# KlokWave_Display.net
KiCad netlist of a schematic drawn in Altium Designer
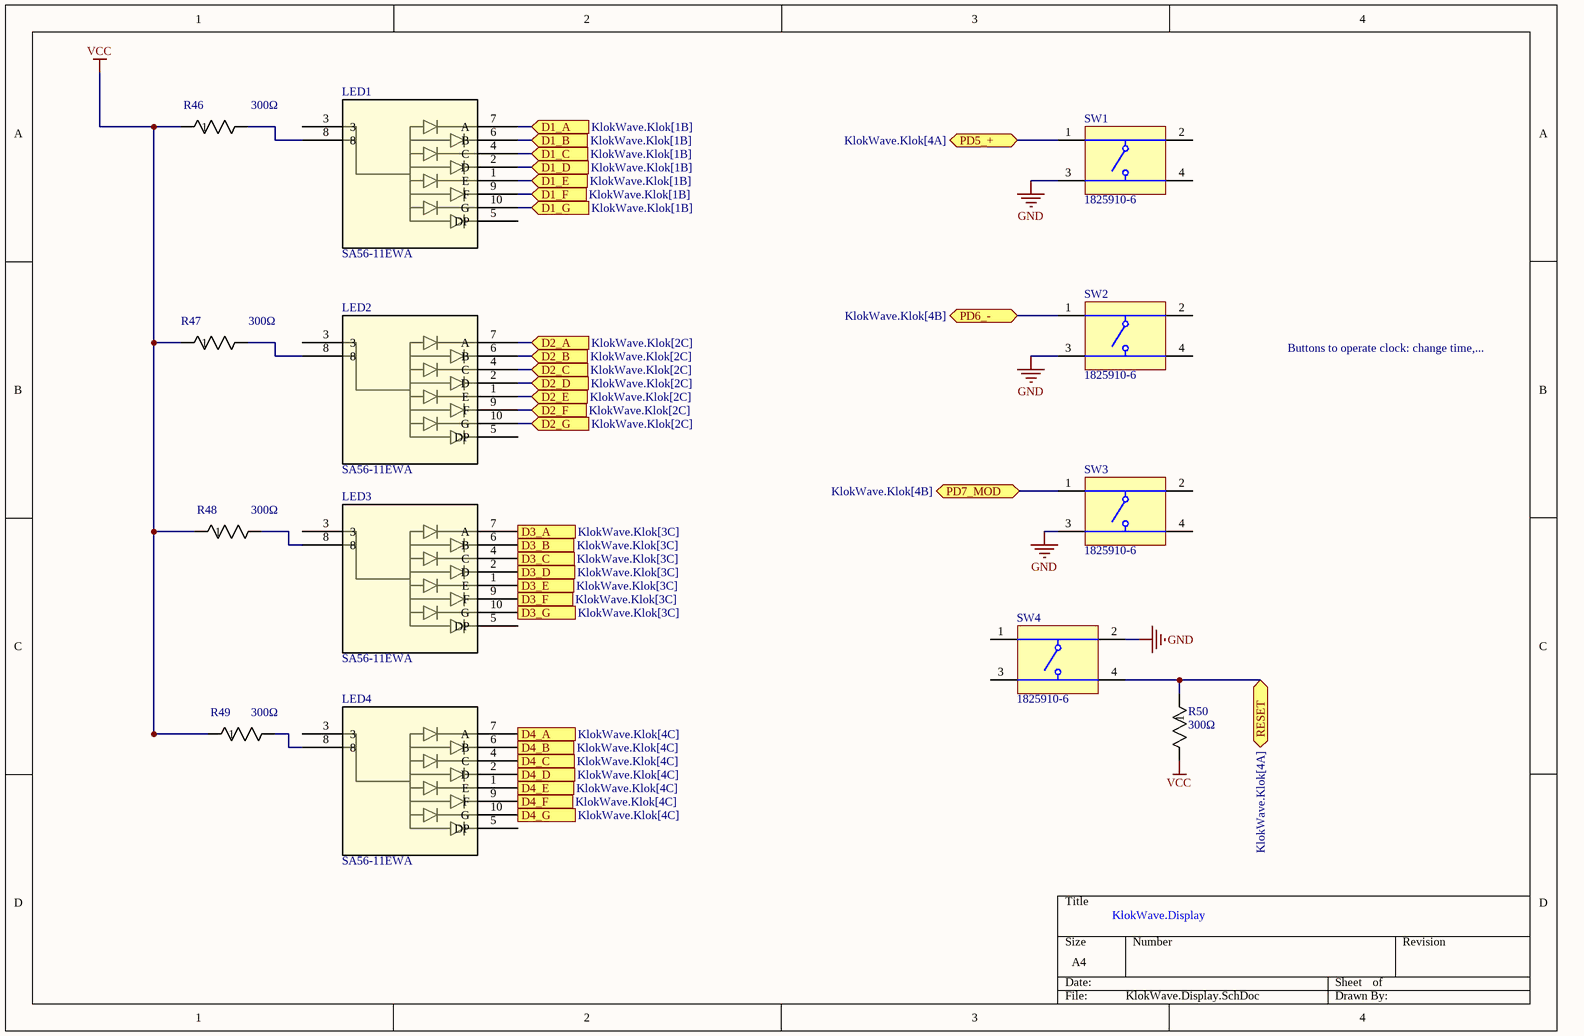
[diagram p0: KlokWave.Display.SchDoc]

(export (version "E")
  (design (tool "Eeschema 10.0.6"))
  (components
    (comp (ref "LED1")
      (value "SA56-11EWA")
      (footprint "THT 7Seg: LED10_SA56-11EWA_KNB")
      (description "THT CA 7SegDisplay")
      (libsource (lib "KlokWave") (part "SA56-11EWA"))
    )
    (comp (ref "LED2")
      (value "SA56-11EWA")
      (footprint "THT 7Seg: LED10_SA56-11EWA_KNB")
      (description "THT CA 7SegDisplay")
      (libsource (lib "KlokWave") (part "SA56-11EWA"))
    )
    (comp (ref "LED3")
      (value "SA56-11EWA")
      (footprint "THT 7Seg: LED10_SA56-11EWA_KNB")
      (description "THT CA 7SegDisplay")
      (libsource (lib "KlokWave") (part "SA56-11EWA"))
    )
    (comp (ref "LED4")
      (value "SA56-11EWA")
      (footprint "THT 7Seg: LED10_SA56-11EWA_KNB")
      (description "THT CA 7SegDisplay")
      (libsource (lib "KlokWave") (part "SA56-11EWA"))
    )
    (comp (ref "R46")
      (value "AC03000003000JAC00")
      (footprint "THT Resistor: RES_AC03_VIS")
      (description "AC03000003000JAC00 Res Wirewound THT")
      (fields (field (name "TOLERANCE") "5%") (field (name "RESISTANCE") "300Ω"))
      (libsource (lib "KlokWave") (part "CMP-00030-39746760-1"))
    )
    (comp (ref "R47")
      (value "AC03000003000JAC00")
      (footprint "THT Resistor: RES_AC03_VIS")
      (description "AC03000003000JAC00 Res Wirewound THT")
      (fields (field (name "TOLERANCE") "5%") (field (name "RESISTANCE") "300Ω"))
      (libsource (lib "KlokWave") (part "CMP-00030-39746760-1"))
    )
    (comp (ref "R48")
      (value "AC03000003000JAC00")
      (footprint "THT Resistor: RES_AC03_VIS")
      (description "AC03000003000JAC00 Res Wirewound THT")
      (fields (field (name "TOLERANCE") "5%") (field (name "RESISTANCE") "300Ω"))
      (libsource (lib "KlokWave") (part "CMP-00030-39746760-1"))
    )
    (comp (ref "R49")
      (value "AC03000003000JAC00")
      (footprint "THT Resistor: RES_AC03_VIS")
      (description "AC03000003000JAC00 Res Wirewound THT")
      (fields (field (name "TOLERANCE") "5%") (field (name "RESISTANCE") "300Ω"))
      (libsource (lib "KlokWave") (part "CMP-00030-39746760-1"))
    )
    (comp (ref "R50")
      (value "AC03000003000JAC00")
      (footprint "THT Resistor: RES_AC03_VIS")
      (description "AC03000003000JAC00 Res Wirewound THT")
      (fields (field (name "TOLERANCE") "5%") (field (name "RESISTANCE") "300Ω"))
      (libsource (lib "KlokWave") (part "CMP-00030-39746760-1"))
    )
    (comp (ref "SW1")
      (value "1825910-6")
      (footprint "THT Button: TECO-1825910-6_V")
      (description "THT Tact Switch, SPST-NO, 0.05 A, -35 to 85 degC, 4-Pin THD, RoHS, Bulk")
      (fields (field (name "MANUFACTURER") "TE Connectivity"))
      (libsource (lib "KlokWave") (part "CMP-1684-00021-1"))
    )
    (comp (ref "SW2")
      (value "1825910-6")
      (footprint "THT Button: TECO-1825910-6_V")
      (description "THT Tact Switch, SPST-NO, 0.05 A, -35 to 85 degC, 4-Pin THD, RoHS, Bulk")
      (fields (field (name "MANUFACTURER") "TE Connectivity"))
      (libsource (lib "KlokWave") (part "CMP-1684-00021-1"))
    )
    (comp (ref "SW3")
      (value "1825910-6")
      (footprint "THT Button: TECO-1825910-6_V")
      (description "THT Tact Switch, SPST-NO, 0.05 A, -35 to 85 degC, 4-Pin THD, RoHS, Bulk")
      (fields (field (name "MANUFACTURER") "TE Connectivity"))
      (libsource (lib "KlokWave") (part "CMP-1684-00021-1"))
    )
    (comp (ref "SW4")
      (value "1825910-6")
      (footprint "THT Button: TECO-1825910-6_V")
      (description "THT Tact Switch, SPST-NO, 0.05 A, -35 to 85 degC, 4-Pin THD, RoHS, Bulk")
      (fields (field (name "MANUFACTURER") "TE Connectivity"))
      (libsource (lib "KlokWave") (part "CMP-1684-00021-1"))
    )
  )
  (nets
    (net (code "1") (name "/D1_A") (class "Default")
      (node (ref "LED1") (pin "7") (pinfunction "A_7") (pintype "passive"))
    )
    (net (code "2") (name "/D1_B") (class "Default")
      (node (ref "LED1") (pin "6") (pinfunction "B_6") (pintype "passive"))
    )
    (net (code "3") (name "/D1_C") (class "Default")
      (node (ref "LED1") (pin "4") (pinfunction "C_4") (pintype "passive"))
    )
    (net (code "4") (name "/D1_D") (class "Default")
      (node (ref "LED1") (pin "2") (pinfunction "D_2") (pintype "passive"))
    )
    (net (code "5") (name "/D1_E") (class "Default")
      (node (ref "LED1") (pin "1") (pinfunction "E_1") (pintype "passive"))
    )
    (net (code "6") (name "/D1_F") (class "Default")
      (node (ref "LED1") (pin "9") (pinfunction "F_9") (pintype "passive"))
    )
    (net (code "7") (name "/D1_G") (class "Default")
      (node (ref "LED1") (pin "10") (pinfunction "G_10") (pintype "passive"))
    )
    (net (code "8") (name "/D2_A") (class "Default")
      (node (ref "LED2") (pin "7") (pinfunction "A_7") (pintype "passive"))
    )
    (net (code "9") (name "/D2_B") (class "Default")
      (node (ref "LED2") (pin "6") (pinfunction "B_6") (pintype "passive"))
    )
    (net (code "10") (name "/D2_C") (class "Default")
      (node (ref "LED2") (pin "4") (pinfunction "C_4") (pintype "passive"))
    )
    (net (code "11") (name "/D2_D") (class "Default")
      (node (ref "LED2") (pin "2") (pinfunction "D_2") (pintype "passive"))
    )
    (net (code "12") (name "/D2_E") (class "Default")
      (node (ref "LED2") (pin "1") (pinfunction "E_1") (pintype "passive"))
    )
    (net (code "13") (name "/D2_F") (class "Default")
      (node (ref "LED2") (pin "9") (pinfunction "F_9") (pintype "passive"))
    )
    (net (code "14") (name "/D2_G") (class "Default")
      (node (ref "LED2") (pin "10") (pinfunction "G_10") (pintype "passive"))
    )
    (net (code "15") (name "/D3_A") (class "Default")
      (node (ref "LED3") (pin "7") (pinfunction "A_7") (pintype "passive"))
    )
    (net (code "16") (name "/D3_B") (class "Default")
      (node (ref "LED3") (pin "6") (pinfunction "B_6") (pintype "passive"))
    )
    (net (code "17") (name "/D3_C") (class "Default")
      (node (ref "LED3") (pin "4") (pinfunction "C_4") (pintype "passive"))
    )
    (net (code "18") (name "/D3_D") (class "Default")
      (node (ref "LED3") (pin "2") (pinfunction "D_2") (pintype "passive"))
    )
    (net (code "19") (name "/D3_E") (class "Default")
      (node (ref "LED3") (pin "1") (pinfunction "E_1") (pintype "passive"))
    )
    (net (code "20") (name "/D3_F") (class "Default")
      (node (ref "LED3") (pin "9") (pinfunction "F_9") (pintype "passive"))
    )
    (net (code "21") (name "/D3_G") (class "Default")
      (node (ref "LED3") (pin "10") (pinfunction "G_10") (pintype "passive"))
    )
    (net (code "22") (name "/D4_A") (class "Default")
      (node (ref "LED4") (pin "7") (pinfunction "A_7") (pintype "passive"))
    )
    (net (code "23") (name "/D4_B") (class "Default")
      (node (ref "LED4") (pin "6") (pinfunction "B_6") (pintype "passive"))
    )
    (net (code "24") (name "/D4_C") (class "Default")
      (node (ref "LED4") (pin "4") (pinfunction "C_4") (pintype "passive"))
    )
    (net (code "25") (name "/D4_D") (class "Default")
      (node (ref "LED4") (pin "2") (pinfunction "D_2") (pintype "passive"))
    )
    (net (code "26") (name "/D4_E") (class "Default")
      (node (ref "LED4") (pin "1") (pinfunction "E_1") (pintype "passive"))
    )
    (net (code "27") (name "/D4_F") (class "Default")
      (node (ref "LED4") (pin "9") (pinfunction "F_9") (pintype "passive"))
    )
    (net (code "28") (name "/D4_G") (class "Default")
      (node (ref "LED4") (pin "10") (pinfunction "G_10") (pintype "passive"))
    )
    (net (code "29") (name "/PD5_+") (class "Default")
      (node (ref "SW1") (pin "1") (pinfunction "1_1") (pintype "passive"))
    )
    (net (code "30") (name "/PD6_-") (class "Default")
      (node (ref "SW2") (pin "1") (pinfunction "1_1") (pintype "passive"))
    )
    (net (code "31") (name "/PD7_MOD") (class "Default")
      (node (ref "SW3") (pin "1") (pinfunction "1_1") (pintype "passive"))
    )
    (net (code "32") (name "/RESET") (class "Default")
      (node (ref "R50") (pin "1") (pinfunction "1_1") (pintype "passive"))
      (node (ref "SW4") (pin "4") (pinfunction "4_4") (pintype "passive"))
    )
    (net (code "33") (name "GND") (class "Default")
      (node (ref "SW1") (pin "3") (pinfunction "3_3") (pintype "passive"))
      (node (ref "SW2") (pin "3") (pinfunction "3_3") (pintype "passive"))
      (node (ref "SW3") (pin "3") (pinfunction "3_3") (pintype "passive"))
      (node (ref "SW4") (pin "2") (pinfunction "2_2") (pintype "passive"))
    )
    (net (code "34") (name "Net-(LED1-Pad8)") (class "Default")
      (node (ref "LED1") (pin "8") (pinfunction "8_8") (pintype "passive"))
      (node (ref "R46") (pin "2") (pinfunction "2_2") (pintype "passive"))
    )
    (net (code "35") (name "Net-(LED2-Pad8)") (class "Default")
      (node (ref "LED2") (pin "8") (pinfunction "8_8") (pintype "passive"))
      (node (ref "R47") (pin "2") (pinfunction "2_2") (pintype "passive"))
    )
    (net (code "36") (name "Net-(LED3-Pad8)") (class "Default")
      (node (ref "LED3") (pin "8") (pinfunction "8_8") (pintype "passive"))
      (node (ref "R48") (pin "2") (pinfunction "2_2") (pintype "passive"))
    )
    (net (code "37") (name "Net-(LED4-Pad8)") (class "Default")
      (node (ref "LED4") (pin "8") (pinfunction "8_8") (pintype "passive"))
      (node (ref "R49") (pin "2") (pinfunction "2_2") (pintype "passive"))
    )
    (net (code "38") (name "VCC") (class "Default")
      (node (ref "R46") (pin "1") (pinfunction "1_1") (pintype "passive"))
      (node (ref "R47") (pin "1") (pinfunction "1_1") (pintype "passive"))
      (node (ref "R48") (pin "1") (pinfunction "1_1") (pintype "passive"))
      (node (ref "R49") (pin "1") (pinfunction "1_1") (pintype "passive"))
      (node (ref "R50") (pin "2") (pinfunction "2_2") (pintype "passive"))
    )
    (net (code "39") (name "unconnected-(LED1-DP-Pad5)") (class "Default")
      (node (ref "LED1") (pin "5") (pinfunction "DP_5") (pintype "passive"))
    )
    (net (code "40") (name "unconnected-(LED1-Pad3)") (class "Default")
      (node (ref "LED1") (pin "3") (pinfunction "3_3") (pintype "passive"))
    )
    (net (code "41") (name "unconnected-(LED2-DP-Pad5)") (class "Default")
      (node (ref "LED2") (pin "5") (pinfunction "DP_5") (pintype "passive"))
    )
    (net (code "42") (name "unconnected-(LED2-Pad3)") (class "Default")
      (node (ref "LED2") (pin "3") (pinfunction "3_3") (pintype "passive"))
    )
    (net (code "43") (name "unconnected-(LED3-DP-Pad5)") (class "Default")
      (node (ref "LED3") (pin "5") (pinfunction "DP_5") (pintype "passive"))
    )
    (net (code "44") (name "unconnected-(LED3-Pad3)") (class "Default")
      (node (ref "LED3") (pin "3") (pinfunction "3_3") (pintype "passive"))
    )
    (net (code "45") (name "unconnected-(LED4-DP-Pad5)") (class "Default")
      (node (ref "LED4") (pin "5") (pinfunction "DP_5") (pintype "passive"))
    )
    (net (code "46") (name "unconnected-(LED4-Pad3)") (class "Default")
      (node (ref "LED4") (pin "3") (pinfunction "3_3") (pintype "passive"))
    )
    (net (code "47") (name "unconnected-(SW1-Pad2)") (class "Default")
      (node (ref "SW1") (pin "2") (pinfunction "2_2") (pintype "passive"))
    )
    (net (code "48") (name "unconnected-(SW1-Pad4)") (class "Default")
      (node (ref "SW1") (pin "4") (pinfunction "4_4") (pintype "passive"))
    )
    (net (code "49") (name "unconnected-(SW2-Pad2)") (class "Default")
      (node (ref "SW2") (pin "2") (pinfunction "2_2") (pintype "passive"))
    )
    (net (code "50") (name "unconnected-(SW2-Pad4)") (class "Default")
      (node (ref "SW2") (pin "4") (pinfunction "4_4") (pintype "passive"))
    )
    (net (code "51") (name "unconnected-(SW3-Pad2)") (class "Default")
      (node (ref "SW3") (pin "2") (pinfunction "2_2") (pintype "passive"))
    )
    (net (code "52") (name "unconnected-(SW3-Pad4)") (class "Default")
      (node (ref "SW3") (pin "4") (pinfunction "4_4") (pintype "passive"))
    )
    (net (code "53") (name "unconnected-(SW4-Pad1)") (class "Default")
      (node (ref "SW4") (pin "1") (pinfunction "1_1") (pintype "passive"))
    )
    (net (code "54") (name "unconnected-(SW4-Pad3)") (class "Default")
      (node (ref "SW4") (pin "3") (pinfunction "3_3") (pintype "passive"))
    )
  )
)
